# SFCRS232.net
KiCad netlist of a schematic drawn in Altium Designer
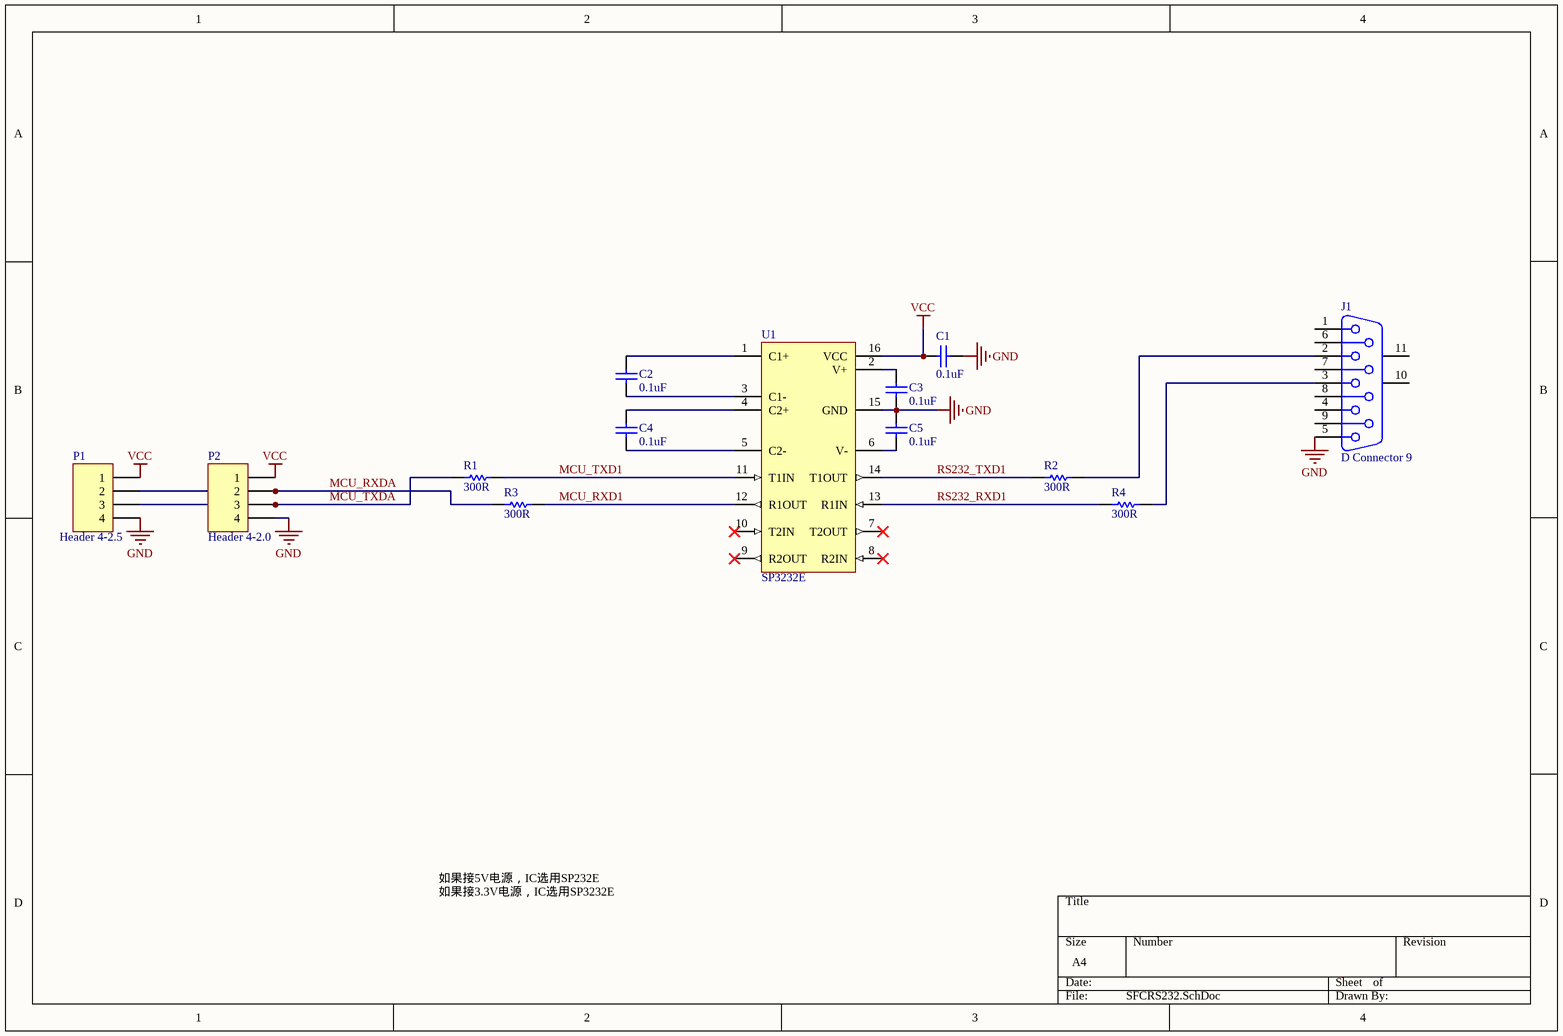
[diagram p0: SFCRS232.SchDoc]

(export (version "E")
  (design (tool "Eeschema 10.0.6"))
  (components
    (comp (ref "C1")
      (value "0.1uF")
      (footprint "CAPC2012M")
      (description "Capacitor")
      (fields (field (name "PUBLISHER") "Altium Limited"))
      (libsource (lib "Miscellaneous Devices") (part "Cap"))
    )
    (comp (ref "C2")
      (value "0.1uF")
      (footprint "CAPC2012M")
      (description "Capacitor")
      (fields (field (name "PUBLISHER") "Altium Limited"))
      (libsource (lib "Miscellaneous Devices") (part "Cap"))
    )
    (comp (ref "C3")
      (value "0.1uF")
      (footprint "CAPC2012M")
      (description "Capacitor")
      (fields (field (name "PUBLISHER") "Altium Limited"))
      (libsource (lib "Miscellaneous Devices") (part "Cap"))
    )
    (comp (ref "C4")
      (value "0.1uF")
      (footprint "CAPC2012M")
      (description "Capacitor")
      (fields (field (name "PUBLISHER") "Altium Limited"))
      (libsource (lib "Miscellaneous Devices") (part "Cap"))
    )
    (comp (ref "C5")
      (value "0.1uF")
      (footprint "CAPC2012M")
      (description "Capacitor")
      (fields (field (name "PUBLISHER") "Altium Limited"))
      (libsource (lib "Miscellaneous Devices") (part "Cap"))
    )
    (comp (ref "J1")
      (value "D Connector 9")
      (footprint "DB9-M")
      (description "串口")
      (fields (field (name "PUBLISHER") "Altium Limited"))
      (libsource (lib "UserSchCon") (part "D Connector 9"))
    )
    (comp (ref "P1")
      (value "Header 4-2.5")
      (footprint "HDR1X4-2.5")
      (description "Header, 4-Pin")
      (fields (field (name "PUBLISHER") "Altium Limited"))
      (libsource (lib "UserSchCon") (part "Header 4"))
    )
    (comp (ref "P2")
      (value "Header 4-2.0")
      (footprint "HDR1X4-2.0")
      (description "Header, 4-Pin")
      (fields (field (name "PUBLISHER") "Altium Limited"))
      (libsource (lib "UserSchCon") (part "Header 4"))
    )
    (comp (ref "R1")
      (value "300R")
      (footprint "RESC2012M")
      (description "Resistor")
      (fields (field (name "PUBLISHER") "Altium Limited"))
      (libsource (lib "Miscellaneous Devices") (part "Res1"))
    )
    (comp (ref "R2")
      (value "300R")
      (footprint "RESC2012M")
      (description "Resistor")
      (fields (field (name "PUBLISHER") "Altium Limited"))
      (libsource (lib "Miscellaneous Devices") (part "Res1"))
    )
    (comp (ref "R3")
      (value "300R")
      (footprint "RESC2012M")
      (description "Resistor")
      (fields (field (name "PUBLISHER") "Altium Limited"))
      (libsource (lib "Miscellaneous Devices") (part "Res1"))
    )
    (comp (ref "R4")
      (value "300R")
      (footprint "RESC2012M")
      (description "Resistor")
      (fields (field (name "PUBLISHER") "Altium Limited"))
      (libsource (lib "Miscellaneous Devices") (part "Res1"))
    )
    (comp (ref "U1")
      (value "SP3232E")
      (footprint "NSO16_M")
      (description "+3.0V+5V Powered, Multi-Channel RS-232 Driver/Receiver")
      (fields (field (name "PUBLISHER") "Altium Limited"))
      (libsource (lib "UserSchDev") (part "SP3232E"))
    )
  )
  (nets
    (net (code "1") (name "/MCU_RXD1") (class "Default")
      (node (ref "R3") (pin "2") (pinfunction "2_2") (pintype "passive"))
      (node (ref "U1") (pin "12") (pinfunction "R1OUT_12") (pintype "output"))
    )
    (net (code "2") (name "/MCU_RXDA") (class "Default")
      (node (ref "P1") (pin "2") (pinfunction "2_2") (pintype "passive"))
      (node (ref "P2") (pin "2") (pinfunction "2_2") (pintype "passive"))
      (node (ref "R3") (pin "1") (pinfunction "1_1") (pintype "passive"))
    )
    (net (code "3") (name "/MCU_TXD1") (class "Default")
      (node (ref "R1") (pin "2") (pinfunction "2_2") (pintype "passive"))
      (node (ref "U1") (pin "11") (pinfunction "T1IN_11") (pintype "input"))
    )
    (net (code "4") (name "/MCU_TXDA") (class "Default")
      (node (ref "P1") (pin "3") (pinfunction "3_3") (pintype "passive"))
      (node (ref "P2") (pin "3") (pinfunction "3_3") (pintype "passive"))
      (node (ref "R1") (pin "1") (pinfunction "1_1") (pintype "passive"))
    )
    (net (code "5") (name "/RS232_RXD1") (class "Default")
      (node (ref "R4") (pin "1") (pinfunction "1_1") (pintype "passive"))
      (node (ref "U1") (pin "13") (pinfunction "R1IN_13") (pintype "input"))
    )
    (net (code "6") (name "/RS232_TXD1") (class "Default")
      (node (ref "R2") (pin "1") (pinfunction "1_1") (pintype "passive"))
      (node (ref "U1") (pin "14") (pinfunction "T1OUT_14") (pintype "output"))
    )
    (net (code "7") (name "GND") (class "Default")
      (node (ref "C1") (pin "1") (pinfunction "1_1") (pintype "passive"))
      (node (ref "C3") (pin "2") (pinfunction "2_2") (pintype "passive"))
      (node (ref "C5") (pin "1") (pinfunction "1_1") (pintype "passive"))
      (node (ref "J1") (pin "5") (pinfunction "5_5") (pintype "passive"))
      (node (ref "P1") (pin "4") (pinfunction "4_4") (pintype "passive"))
      (node (ref "P2") (pin "4") (pinfunction "4_4") (pintype "passive"))
      (node (ref "U1") (pin "15") (pinfunction "GND_15") (pintype "power_in"))
    )
    (net (code "8") (name "Net-(J1-Pad2)") (class "Default")
      (node (ref "J1") (pin "2") (pinfunction "2_2") (pintype "passive"))
      (node (ref "R2") (pin "2") (pinfunction "2_2") (pintype "passive"))
    )
    (net (code "9") (name "Net-(J1-Pad3)") (class "Default")
      (node (ref "J1") (pin "3") (pinfunction "3_3") (pintype "passive"))
      (node (ref "R4") (pin "2") (pinfunction "2_2") (pintype "passive"))
    )
    (net (code "10") (name "Net-(U1-C1+)") (class "Default")
      (node (ref "C2") (pin "2") (pinfunction "2_2") (pintype "passive"))
      (node (ref "U1") (pin "1") (pinfunction "C1+_1") (pintype "passive"))
    )
    (net (code "11") (name "Net-(U1-C1-)") (class "Default")
      (node (ref "C2") (pin "1") (pinfunction "1_1") (pintype "passive"))
      (node (ref "U1") (pin "3") (pinfunction "C1-_3") (pintype "passive"))
    )
    (net (code "12") (name "Net-(U1-C2+)") (class "Default")
      (node (ref "C4") (pin "2") (pinfunction "2_2") (pintype "passive"))
      (node (ref "U1") (pin "4") (pinfunction "C2+_4") (pintype "passive"))
    )
    (net (code "13") (name "Net-(U1-C2-)") (class "Default")
      (node (ref "C4") (pin "1") (pinfunction "1_1") (pintype "passive"))
      (node (ref "U1") (pin "5") (pinfunction "C2-_5") (pintype "passive"))
    )
    (net (code "14") (name "Net-(U1-V+)") (class "Default")
      (node (ref "C3") (pin "1") (pinfunction "1_1") (pintype "passive"))
      (node (ref "U1") (pin "2") (pinfunction "V+_2") (pintype "power_in"))
    )
    (net (code "15") (name "Net-(U1-V-)") (class "Default")
      (node (ref "C5") (pin "2") (pinfunction "2_2") (pintype "passive"))
      (node (ref "U1") (pin "6") (pinfunction "V-_6") (pintype "power_in"))
    )
    (net (code "16") (name "VCC") (class "Default")
      (node (ref "C1") (pin "2") (pinfunction "2_2") (pintype "passive"))
      (node (ref "P1") (pin "1") (pinfunction "1_1") (pintype "passive"))
      (node (ref "P2") (pin "1") (pinfunction "1_1") (pintype "passive"))
      (node (ref "U1") (pin "16") (pinfunction "VCC_16") (pintype "power_in"))
    )
    (net (code "17") (name "unconnected-(J1-MH1-Pad10)") (class "Default")
      (node (ref "J1") (pin "10") (pinfunction "MH1_10") (pintype "passive"))
    )
    (net (code "18") (name "unconnected-(J1-MH2-Pad11)") (class "Default")
      (node (ref "J1") (pin "11") (pinfunction "MH2_11") (pintype "passive"))
    )
    (net (code "19") (name "unconnected-(J1-Pad1)") (class "Default")
      (node (ref "J1") (pin "1") (pinfunction "1_1") (pintype "passive"))
    )
    (net (code "20") (name "unconnected-(J1-Pad4)") (class "Default")
      (node (ref "J1") (pin "4") (pinfunction "4_4") (pintype "passive"))
    )
    (net (code "21") (name "unconnected-(J1-Pad6)") (class "Default")
      (node (ref "J1") (pin "6") (pinfunction "6_6") (pintype "passive"))
    )
    (net (code "22") (name "unconnected-(J1-Pad7)") (class "Default")
      (node (ref "J1") (pin "7") (pinfunction "7_7") (pintype "passive"))
    )
    (net (code "23") (name "unconnected-(J1-Pad8)") (class "Default")
      (node (ref "J1") (pin "8") (pinfunction "8_8") (pintype "passive"))
    )
    (net (code "24") (name "unconnected-(J1-Pad9)") (class "Default")
      (node (ref "J1") (pin "9") (pinfunction "9_9") (pintype "passive"))
    )
    (net (code "25") (name "unconnected-(U1-R2IN-Pad8)") (class "Default")
      (node (ref "U1") (pin "8") (pinfunction "R2IN_8") (pintype "input+no_connect"))
    )
    (net (code "26") (name "unconnected-(U1-R2OUT-Pad9)") (class "Default")
      (node (ref "U1") (pin "9") (pinfunction "R2OUT_9") (pintype "output+no_connect"))
    )
    (net (code "27") (name "unconnected-(U1-T2IN-Pad10)") (class "Default")
      (node (ref "U1") (pin "10") (pinfunction "T2IN_10") (pintype "input+no_connect"))
    )
    (net (code "28") (name "unconnected-(U1-T2OUT-Pad7)") (class "Default")
      (node (ref "U1") (pin "7") (pinfunction "T2OUT_7") (pintype "output+no_connect"))
    )
  )
)
